# NS_ARM_Control_01_10_2018.net
KiCad netlist of a schematic drawn in EAGLE
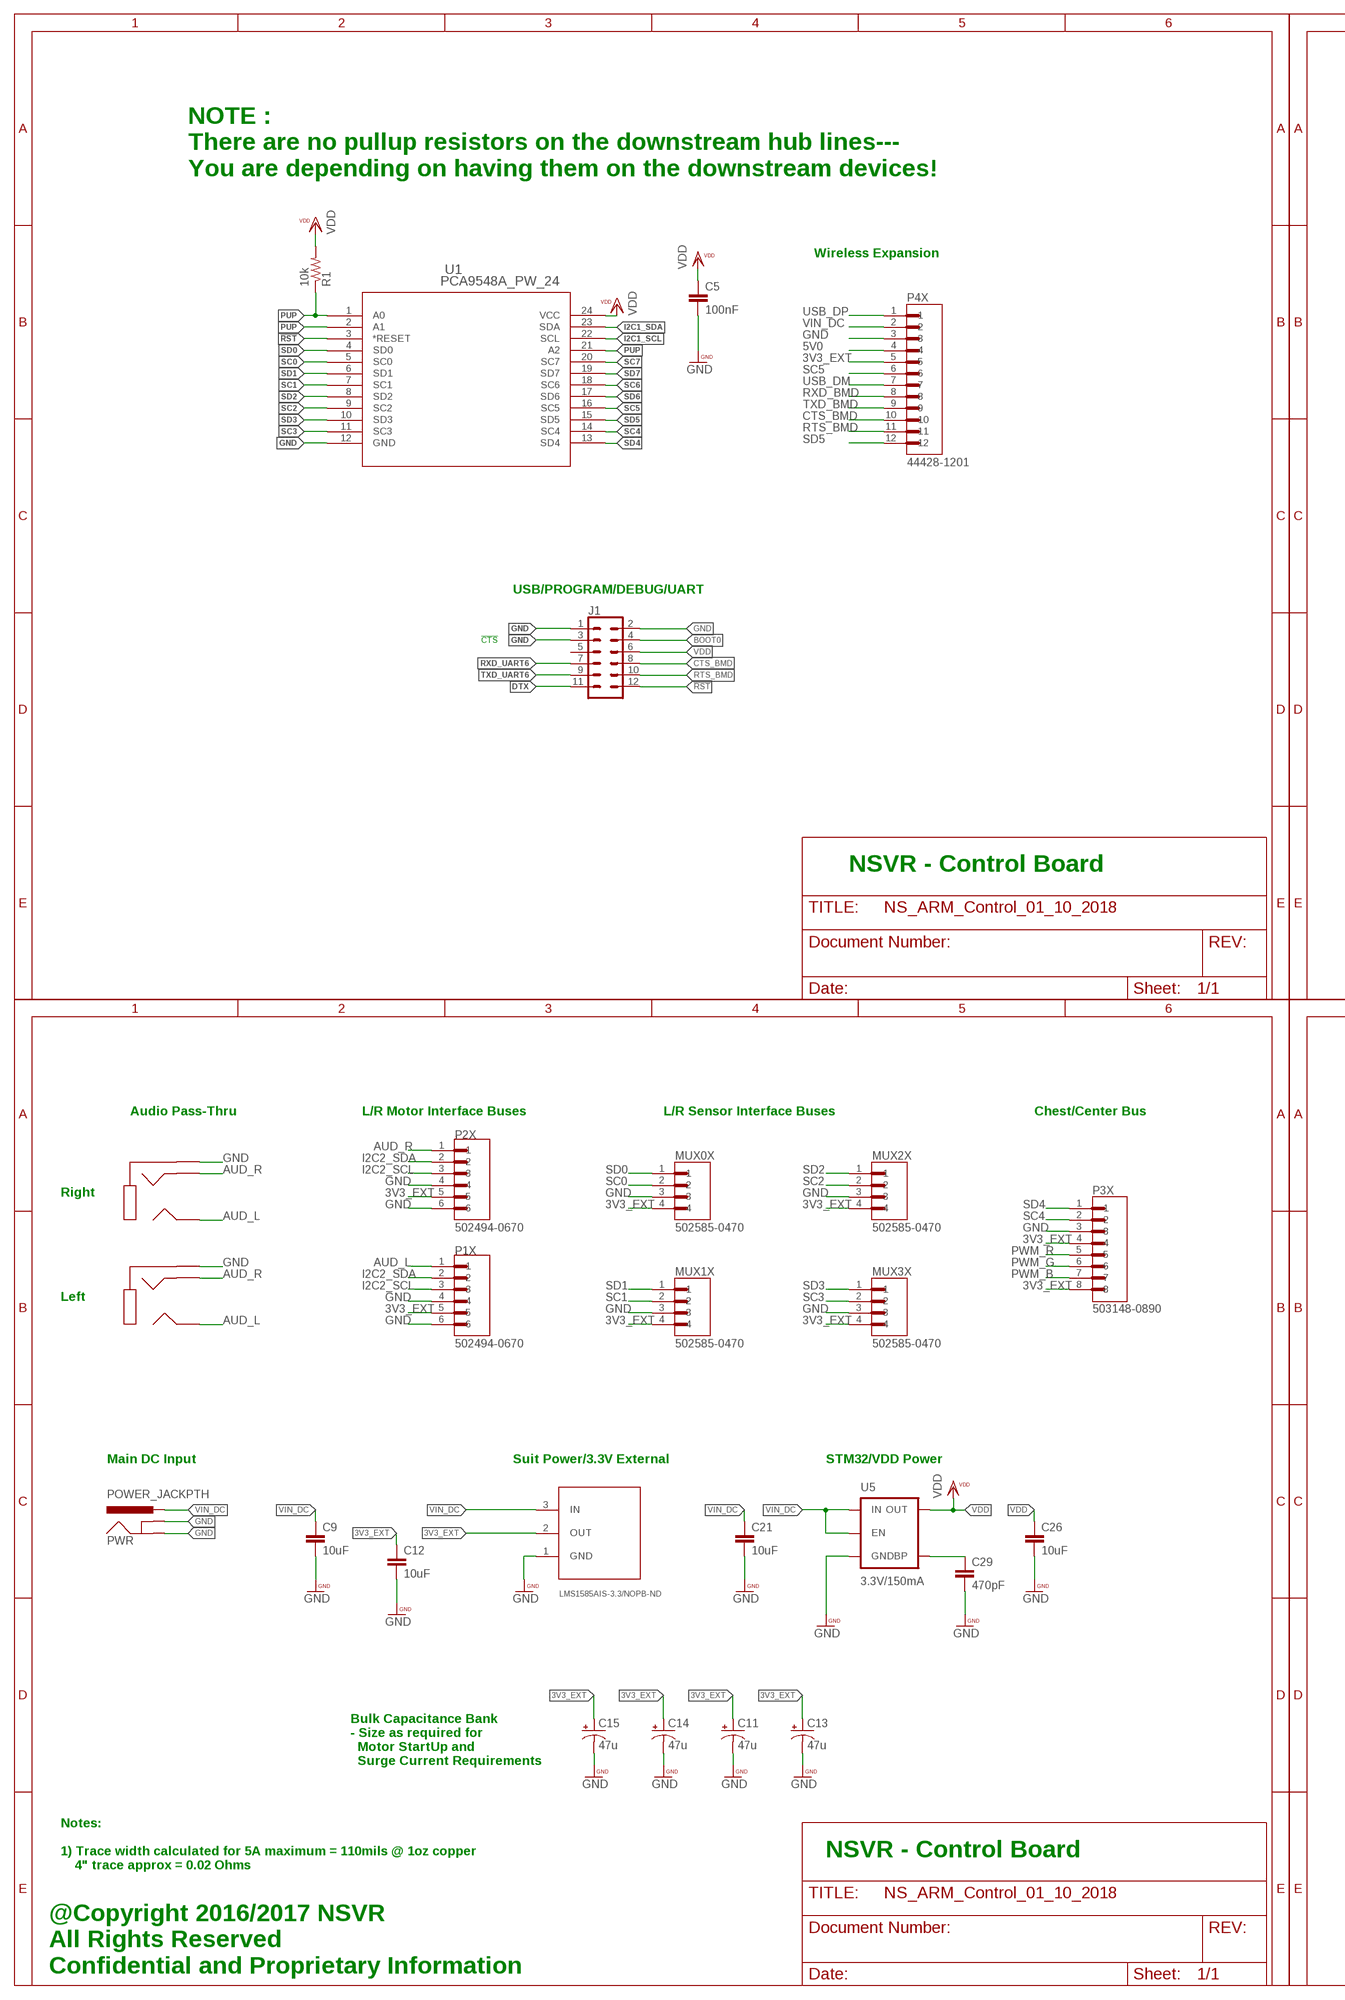
[diagram p0: schematic, sheet 1, part 1 of 2]
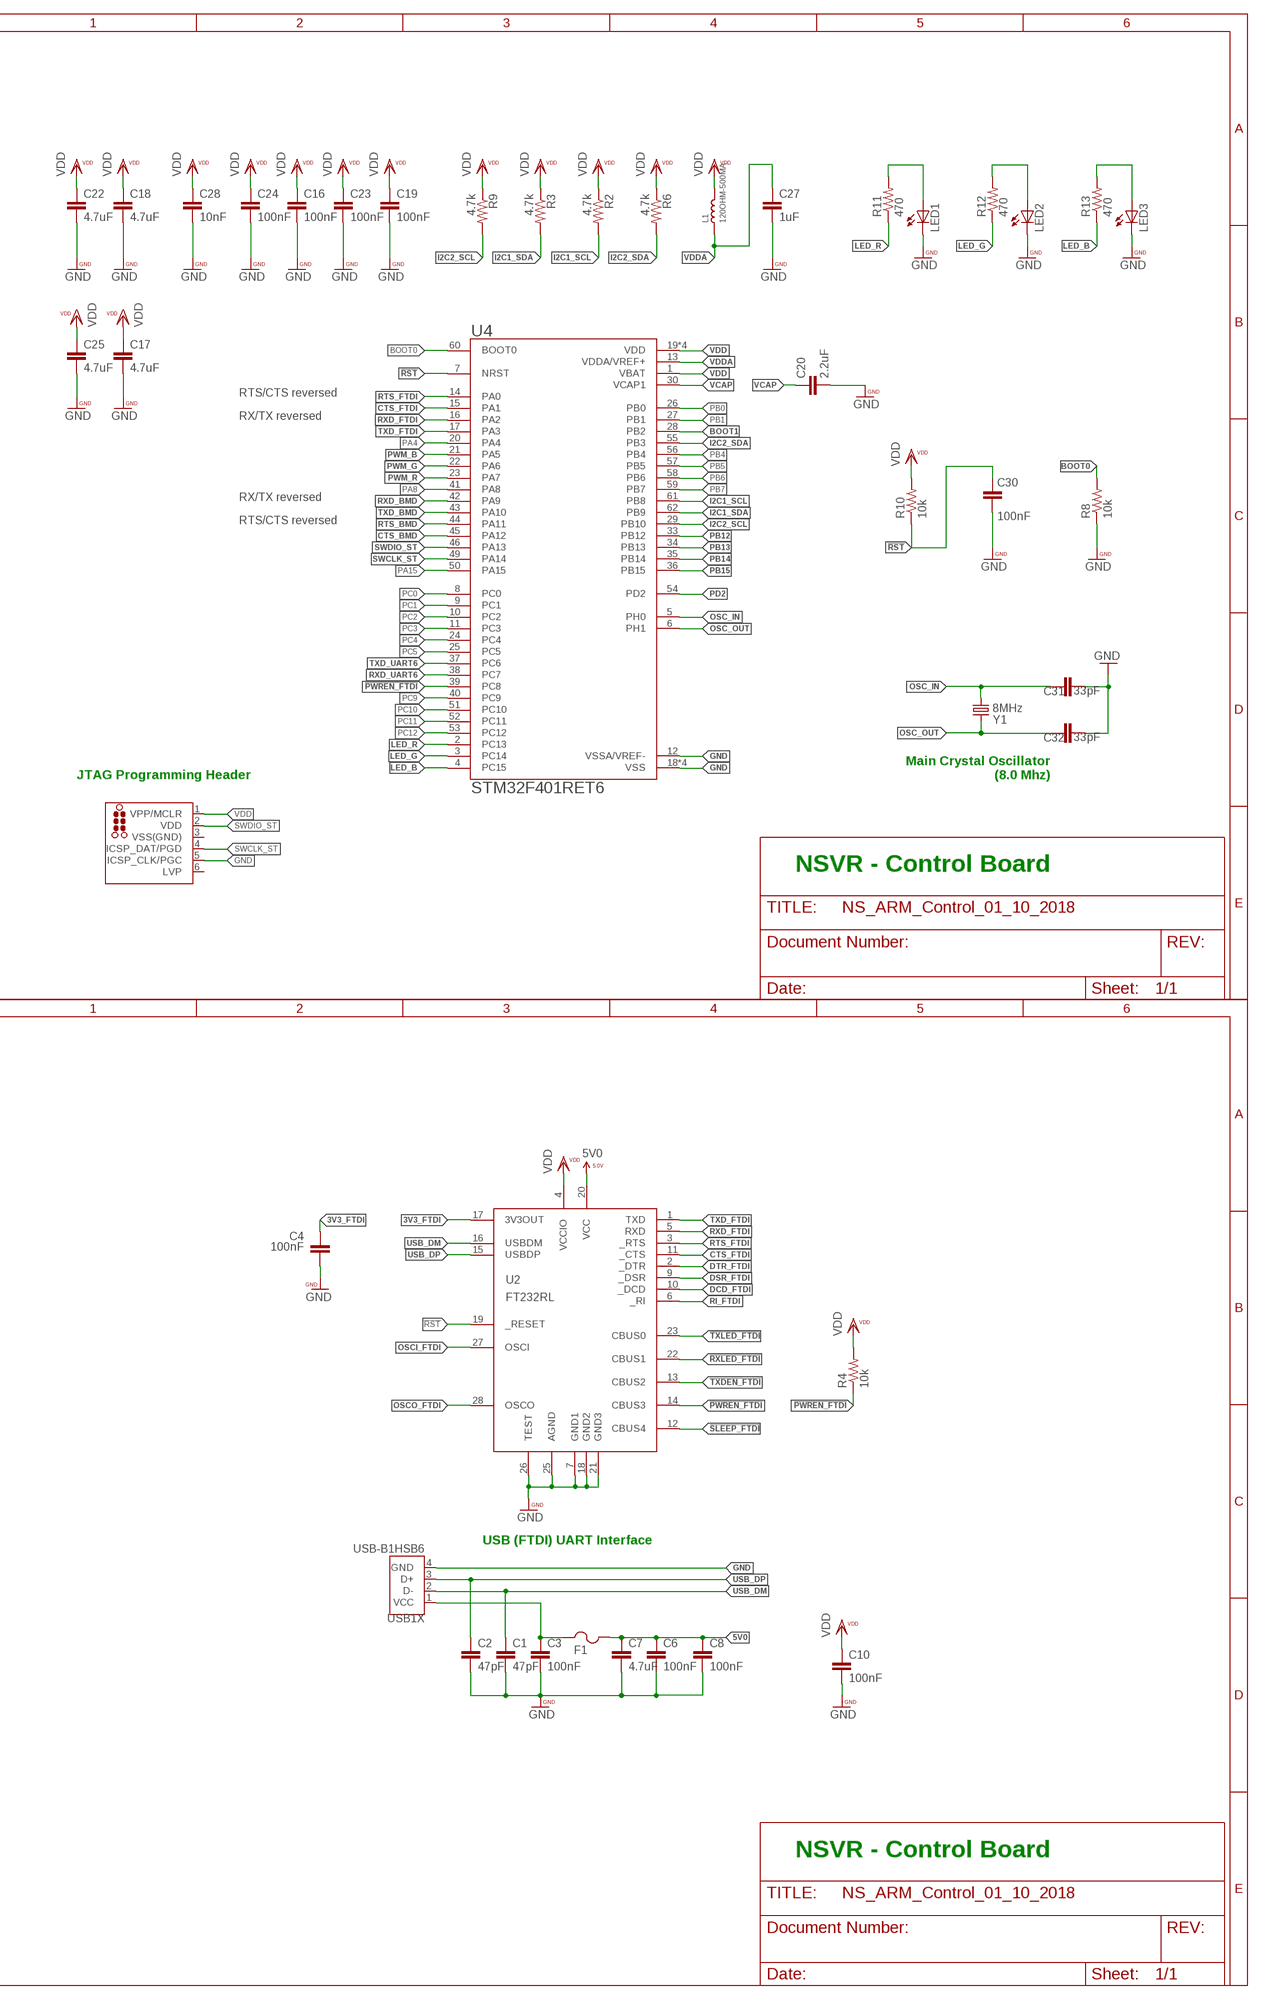
[diagram p1: schematic, sheet 1, part 2 of 2]

(export (version "E")
  (design (tool "Eeschema 10.0.6"))
  (components
    (comp (ref "C1")
      (value "47pF")
      (footprint "eagle-import:0402-CAP")
      (libsource (lib "eagle-import") (part "CAP0402-CAP"))
    )
    (comp (ref "C2")
      (value "47pF")
      (footprint "eagle-import:0402-CAP")
      (libsource (lib "eagle-import") (part "CAP0402-CAP"))
    )
    (comp (ref "C3")
      (value "100nF")
      (footprint "eagle-import:0402-CAP")
      (libsource (lib "eagle-import") (part "CAP0402-CAP"))
    )
    (comp (ref "C4")
      (value "100nF")
      (footprint "eagle-import:0402-CAP")
      (libsource (lib "eagle-import") (part "CAP0402-CAP"))
    )
    (comp (ref "C5")
      (value "100nF")
      (footprint "eagle-import:0402-CAP")
      (libsource (lib "eagle-import") (part "CAP0402-CAP"))
    )
    (comp (ref "C6")
      (value "100nF")
      (footprint "eagle-import:0402-CAP")
      (libsource (lib "eagle-import") (part "CAP0402-CAP"))
    )
    (comp (ref "C7")
      (value "4.7uF")
      (footprint "eagle-import:0402-CAP")
      (libsource (lib "eagle-import") (part "CAP0402-CAP"))
    )
    (comp (ref "C8")
      (value "100nF")
      (footprint "eagle-import:0402-CAP")
      (libsource (lib "eagle-import") (part "CAP0402-CAP"))
    )
    (comp (ref "C9")
      (value "10uF")
      (footprint "eagle-import:0603-CAP")
      (libsource (lib "eagle-import") (part "CAP0603-CAP"))
    )
    (comp (ref "C10")
      (value "100nF")
      (footprint "eagle-import:0402-CAP")
      (libsource (lib "eagle-import") (part "CAP0402-CAP"))
    )
    (comp (ref "C11")
      (value "47u")
      (footprint "eagle-import:PANASONIC_D")
      (libsource (lib "eagle-import") (part "CAP_POLD"))
    )
    (comp (ref "C12")
      (value "10uF")
      (footprint "eagle-import:0603-CAP")
      (libsource (lib "eagle-import") (part "CAP0603-CAP"))
    )
    (comp (ref "C13")
      (value "47u")
      (footprint "eagle-import:PANASONIC_D")
      (libsource (lib "eagle-import") (part "CAP_POLD"))
    )
    (comp (ref "C14")
      (value "47u")
      (footprint "eagle-import:PANASONIC_D")
      (libsource (lib "eagle-import") (part "CAP_POLD"))
    )
    (comp (ref "C15")
      (value "47u")
      (footprint "eagle-import:PANASONIC_D")
      (libsource (lib "eagle-import") (part "CAP_POLD"))
    )
    (comp (ref "C16")
      (value "100nF")
      (footprint "eagle-import:0402-CAP")
      (libsource (lib "eagle-import") (part "CAP0402-CAP"))
    )
    (comp (ref "C17")
      (value "4.7uF")
      (footprint "eagle-import:0402-CAP")
      (libsource (lib "eagle-import") (part "CAP0402-CAP"))
    )
    (comp (ref "C18")
      (value "4.7uF")
      (footprint "eagle-import:0402-CAP")
      (libsource (lib "eagle-import") (part "CAP0402-CAP"))
    )
    (comp (ref "C19")
      (value "100nF")
      (footprint "eagle-import:0402-CAP")
      (libsource (lib "eagle-import") (part "CAP0402-CAP"))
    )
    (comp (ref "C20")
      (value "2.2uF")
      (footprint "eagle-import:0402-CAP")
      (libsource (lib "eagle-import") (part "CAP0402-CAP"))
    )
    (comp (ref "C21")
      (value "10uF")
      (footprint "eagle-import:0603-CAP")
      (libsource (lib "eagle-import") (part "CAP0603-CAP"))
    )
    (comp (ref "C22")
      (value "4.7uF")
      (footprint "eagle-import:0402-CAP")
      (libsource (lib "eagle-import") (part "CAP0402-CAP"))
    )
    (comp (ref "C23")
      (value "100nF")
      (footprint "eagle-import:0402-CAP")
      (libsource (lib "eagle-import") (part "CAP0402-CAP"))
    )
    (comp (ref "C24")
      (value "100nF")
      (footprint "eagle-import:0402-CAP")
      (libsource (lib "eagle-import") (part "CAP0402-CAP"))
    )
    (comp (ref "C25")
      (value "4.7uF")
      (footprint "eagle-import:0402-CAP")
      (libsource (lib "eagle-import") (part "CAP0402-CAP"))
    )
    (comp (ref "C26")
      (value "10uF")
      (footprint "eagle-import:0603-CAP")
      (libsource (lib "eagle-import") (part "CAP0603-CAP"))
    )
    (comp (ref "C27")
      (value "1uF")
      (footprint "eagle-import:0402-CAP")
      (libsource (lib "eagle-import") (part "CAP0402-CAP"))
    )
    (comp (ref "C28")
      (value "10nF")
      (footprint "eagle-import:0402-CAP")
      (libsource (lib "eagle-import") (part "CAP0402-CAP"))
    )
    (comp (ref "C29")
      (value "470pF")
      (footprint "eagle-import:0402-CAP")
      (libsource (lib "eagle-import") (part "CAP0402-CAP"))
    )
    (comp (ref "C30")
      (value "100nF")
      (footprint "eagle-import:0402-CAP")
      (libsource (lib "eagle-import") (part "CAP0402-CAP"))
    )
    (comp (ref "C31")
      (value "33pF")
      (footprint "eagle-import:0402-CAP")
      (libsource (lib "eagle-import") (part "CAP0402-CAP"))
    )
    (comp (ref "C32")
      (value "33pF")
      (footprint "eagle-import:0402-CAP")
      (libsource (lib "eagle-import") (part "CAP0402-CAP"))
    )
    (comp (ref "F1")
      (value "1206L050YR")
      (footprint "eagle-import:1206LSERIES")
      (fields (field (name "COPYRIGHT") "Copyright C 2015 Accelerated Designs. All rights reserved"))
      (libsource (lib "eagle-import") (part "1206L050YR"))
    )
    (comp (ref "J1")
      (value "CONN_06X2SMD_FEMALE")
      (footprint "eagle-import:2X6_SMD")
      (libsource (lib "eagle-import") (part "CONN_06X2SMD_FEMALE"))
    )
    (comp (ref "J_ST")
      (value "TC2030-MCP-NL")
      (footprint "eagle-import:TC2030-MCP-NL")
      (libsource (lib "eagle-import") (part "TC2030-MCP-NL"))
    )
    (comp (ref "L1")
      (value "120OHM-500MA")
      (footprint "eagle-import:L0603")
      (fields (field (name "MPN") "BLM18AG121SN1D"))
      (libsource (lib "eagle-import") (part "SMD-FERRITE-CHIP-120-OHM-500MA(0603)"))
    )
    (comp (ref "LED1")
      (value "LEDCHIP-LED0603")
      (footprint "eagle-import:CHIP-LED0603")
      (libsource (lib "eagle-import") (part "LEDCHIP-LED0603"))
    )
    (comp (ref "LED2")
      (value "LEDCHIP-LED0603")
      (footprint "eagle-import:CHIP-LED0603")
      (libsource (lib "eagle-import") (part "LEDCHIP-LED0603"))
    )
    (comp (ref "LED3")
      (value "LEDCHIP-LED0603")
      (footprint "eagle-import:CHIP-LED0603")
      (libsource (lib "eagle-import") (part "LEDCHIP-LED0603"))
    )
    (comp (ref "MUX0X")
      (value "502585-0470")
      (footprint "eagle-import:MOLEX_502585-0470")
      (fields (field (name "MF") "Molex"))
      (libsource (lib "eagle-import") (part "502585-0470"))
    )
    (comp (ref "MUX1X")
      (value "502585-0470")
      (footprint "eagle-import:MOLEX_502585-0470")
      (fields (field (name "MF") "Molex"))
      (libsource (lib "eagle-import") (part "502585-0470"))
    )
    (comp (ref "MUX2X")
      (value "502585-0470")
      (footprint "eagle-import:MOLEX_502585-0470")
      (fields (field (name "MF") "Molex"))
      (libsource (lib "eagle-import") (part "502585-0470"))
    )
    (comp (ref "MUX3X")
      (value "502585-0470")
      (footprint "eagle-import:MOLEX_502585-0470")
      (fields (field (name "MF") "Molex"))
      (libsource (lib "eagle-import") (part "502585-0470"))
    )
    (comp (ref "P1X")
      (value "502494-0670")
      (footprint "eagle-import:MOLEX_502494-0670")
      (fields (field (name "MF") "Molex"))
      (libsource (lib "eagle-import") (part "502494-0670"))
    )
    (comp (ref "P2X")
      (value "502494-0670")
      (footprint "eagle-import:MOLEX_502494-0670")
      (fields (field (name "MF") "Molex"))
      (libsource (lib "eagle-import") (part "502494-0670"))
    )
    (comp (ref "P3X")
      (value "503148-0890")
      (footprint "eagle-import:MOLEX_503148-0890")
      (fields (field (name "MF") "Molex"))
      (libsource (lib "eagle-import") (part "503148-0890"))
    )
    (comp (ref "P4X")
      (value "44428-1201")
      (footprint "eagle-import:MOLEX_44428-1201")
      (fields (field (name "MF") "Molex"))
      (libsource (lib "eagle-import") (part "44428-1201"))
    )
    (comp (ref "PJ1")
      (value "SJ1-3513N")
      (footprint "eagle-import:SJ1-351XN")
      (libsource (lib "eagle-import") (part "SJ1-3513N"))
    )
    (comp (ref "PJ2")
      (value "SJ1-3513N")
      (footprint "eagle-import:SJ1-351XN")
      (libsource (lib "eagle-import") (part "SJ1-3513N"))
    )
    (comp (ref "PWR")
      (value "POWER_JACKPTH")
      (footprint "eagle-import:POWER_JACK_PTH")
      (libsource (lib "eagle-import") (part "POWER_JACKPTH"))
    )
    (comp (ref "R1")
      (value "10k")
      (footprint "eagle-import:EIA-0402")
      (libsource (lib "eagle-import") (part "RESISTOR0402-TYP"))
    )
    (comp (ref "R2")
      (value "4.7k")
      (footprint "eagle-import:EIA-0402")
      (libsource (lib "eagle-import") (part "RESISTOR0402-TYP"))
    )
    (comp (ref "R3")
      (value "4.7k")
      (footprint "eagle-import:EIA-0402")
      (libsource (lib "eagle-import") (part "RESISTOR0402-TYP"))
    )
    (comp (ref "R4")
      (value "10k")
      (footprint "eagle-import:EIA-0402")
      (libsource (lib "eagle-import") (part "RESISTOR0402-TYP"))
    )
    (comp (ref "R6")
      (value "4.7k")
      (footprint "eagle-import:EIA-0402")
      (libsource (lib "eagle-import") (part "RESISTOR0402-TYP"))
    )
    (comp (ref "R8")
      (value "10k")
      (footprint "eagle-import:EIA-0402")
      (libsource (lib "eagle-import") (part "RESISTOR0402-TYP"))
    )
    (comp (ref "R9")
      (value "4.7k")
      (footprint "eagle-import:EIA-0402")
      (libsource (lib "eagle-import") (part "RESISTOR0402-TYP"))
    )
    (comp (ref "R10")
      (value "10k")
      (footprint "eagle-import:EIA-0402")
      (libsource (lib "eagle-import") (part "RESISTOR0402-TYP"))
    )
    (comp (ref "R11")
      (value "470")
      (footprint "eagle-import:EIA-0402")
      (libsource (lib "eagle-import") (part "RESISTOR0402-TYP"))
    )
    (comp (ref "R12")
      (value "470")
      (footprint "eagle-import:EIA-0402")
      (libsource (lib "eagle-import") (part "RESISTOR0402-TYP"))
    )
    (comp (ref "R13")
      (value "470")
      (footprint "eagle-import:EIA-0402")
      (libsource (lib "eagle-import") (part "RESISTOR0402-TYP"))
    )
    (comp (ref "U1")
      (value "PCA9548A_PW_24")
      (footprint "eagle-import:PW24")
      (fields
        (field (name "GENERIC_PART_NUMBER") "PCA9548A")
        (field (name "MANUFACTURER") "Texas Instruments")
        (field (name "MANUFACTURER_PART_NUMBER") "pca9548a_pw_24")
      )
      (libsource (lib "eagle-import") (part "PCA9548A_PW_24"))
    )
    (comp (ref "U2")
      (value "FT232RL")
      (footprint "eagle-import:SSOP28DB")
      (libsource (lib "eagle-import") (part "FT232RL"))
    )
    (comp (ref "U3")
      (value "LMS1585AIS-3.3/NOPB-ND")
      (footprint "eagle-import:TO254P1524X483-4N")
      (libsource (lib "eagle-import") (part "LMS1585AIS-3.3/NOPB-ND"))
    )
    (comp (ref "U4")
      (value "STM32F401RET6")
      (footprint "eagle-import:QFP50P1200X1200X160-64N")
      (fields (field (name "MF") "STMicroelectronics"))
      (libsource (lib "eagle-import") (part "STM32F401RET6"))
    )
    (comp (ref "U5")
      (value "3.3V/150mA")
      (footprint "eagle-import:SOT23-5")
      (libsource (lib "eagle-import") (part "V_REG_MIC52053.3V"))
    )
    (comp (ref "USB1X")
      (value "USB-B1HSB6")
      (footprint "eagle-import:OST_USB-B1HSB6")
      (fields (field (name "MF") "On Shore Technology"))
      (libsource (lib "eagle-import") (part "USB-B1HSB6"))
    )
    (comp (ref "Y1")
      (value "8MHz")
      (footprint "eagle-import:CRYSTAL-SMD-5X3")
      (libsource (lib "eagle-import") (part "CRYSTAL5X3"))
    )
  )
  (nets
    (net (code "1") (name "/AUD_L") (class "Default")
      (node (ref "P1X") (pin "1") (pinfunction "1_1") (pintype "passive"))
      (node (ref "PJ1") (pin "2") (pinfunction "2_2") (pintype "bidirectional"))
      (node (ref "PJ2") (pin "2") (pinfunction "2_2") (pintype "bidirectional"))
    )
    (net (code "2") (name "/AUD_R") (class "Default")
      (node (ref "P2X") (pin "1") (pinfunction "1_1") (pintype "passive"))
      (node (ref "PJ1") (pin "3") (pinfunction "3_3") (pintype "bidirectional"))
      (node (ref "PJ2") (pin "3") (pinfunction "3_3") (pintype "bidirectional"))
    )
    (net (code "3") (name "/VSS(GND)") (class "Default")
      (node (ref "J_ST") (pin "3") (pinfunction "VSS(GND)_3") (pintype "power_in"))
    )
    (net (code "4") (name "/~{PWREN_FTDI}") (class "Default")
      (node (ref "R4") (pin "1") (pinfunction "1_1") (pintype "passive"))
      (node (ref "U2") (pin "14") (pinfunction "CBUS3_14") (pintype "bidirectional"))
      (node (ref "U4") (pin "39") (pinfunction "PC8_39") (pintype "bidirectional"))
    )
    (net (code "5") (name "/~{RST}") (class "Default")
      (node (ref "C30") (pin "1") (pinfunction "1_1") (pintype "passive"))
      (node (ref "J1") (pin "12") (pinfunction "12_12") (pintype "passive"))
      (node (ref "R10") (pin "1") (pinfunction "1_1") (pintype "passive"))
      (node (ref "U1") (pin "3") (pinfunction "*RESET_3") (pintype "input"))
      (node (ref "U2") (pin "19") (pinfunction "_RESET_19") (pintype "input"))
      (node (ref "U4") (pin "7") (pinfunction "NRST_7") (pintype "bidirectional"))
    )
    (net (code "6") (name "/~{RXLED_FTDI}") (class "Default")
      (node (ref "U2") (pin "22") (pinfunction "CBUS1_22") (pintype "bidirectional"))
    )
    (net (code "7") (name "/~{SLEEP_FTDI}") (class "Default")
      (node (ref "U2") (pin "12") (pinfunction "CBUS4_12") (pintype "bidirectional"))
    )
    (net (code "8") (name "/~{TXDEN_FTDI}") (class "Default")
      (node (ref "U2") (pin "13") (pinfunction "CBUS2_13") (pintype "bidirectional"))
    )
    (net (code "9") (name "/~{TXLED_FTDI}") (class "Default")
      (node (ref "U2") (pin "23") (pinfunction "CBUS0_23") (pintype "bidirectional"))
    )
    (net (code "10") (name "3V3_EXT") (class "Default")
      (node (ref "C11") (pin "+") (pinfunction "+_+") (pintype "passive"))
      (node (ref "C12") (pin "1") (pinfunction "1_1") (pintype "passive"))
      (node (ref "C13") (pin "+") (pinfunction "+_+") (pintype "passive"))
      (node (ref "C14") (pin "+") (pinfunction "+_+") (pintype "passive"))
      (node (ref "C15") (pin "+") (pinfunction "+_+") (pintype "passive"))
      (node (ref "MUX0X") (pin "4") (pinfunction "4_4") (pintype "passive"))
      (node (ref "MUX1X") (pin "4") (pinfunction "4_4") (pintype "passive"))
      (node (ref "MUX2X") (pin "4") (pinfunction "4_4") (pintype "passive"))
      (node (ref "MUX3X") (pin "4") (pinfunction "4_4") (pintype "passive"))
      (node (ref "P1X") (pin "5") (pinfunction "5_5") (pintype "passive"))
      (node (ref "P2X") (pin "5") (pinfunction "5_5") (pintype "passive"))
      (node (ref "P3X") (pin "4") (pinfunction "4_4") (pintype "passive"))
      (node (ref "P3X") (pin "8") (pinfunction "8_8") (pintype "passive"))
      (node (ref "P4X") (pin "5") (pinfunction "5_5") (pintype "passive"))
      (node (ref "U3") (pin "2") (pinfunction "OUT_2") (pintype "bidirectional"))
    )
    (net (code "11") (name "3V3_FTDI") (class "Default")
      (node (ref "C4") (pin "1") (pinfunction "1_1") (pintype "passive"))
      (node (ref "U2") (pin "17") (pinfunction "3V3OUT_17") (pintype "output"))
    )
    (net (code "12") (name "5V0") (class "Default")
      (node (ref "C6") (pin "1") (pinfunction "1_1") (pintype "passive"))
      (node (ref "C7") (pin "1") (pinfunction "1_1") (pintype "passive"))
      (node (ref "C8") (pin "1") (pinfunction "1_1") (pintype "passive"))
      (node (ref "F1") (pin "2") (pinfunction "2_2") (pintype "passive"))
      (node (ref "P4X") (pin "4") (pinfunction "4_4") (pintype "passive"))
      (node (ref "U2") (pin "20") (pinfunction "VCC_20") (pintype "power_in"))
    )
    (net (code "13") (name "BOOT0") (class "Default")
      (node (ref "J1") (pin "4") (pinfunction "4_4") (pintype "passive"))
      (node (ref "R8") (pin "2") (pinfunction "2_2") (pintype "passive"))
      (node (ref "U4") (pin "60") (pinfunction "BOOT0_60") (pintype "input"))
    )
    (net (code "14") (name "BOOT1") (class "Default")
      (node (ref "U4") (pin "28") (pinfunction "PB2_28") (pintype "bidirectional"))
    )
    (net (code "15") (name "CTS_BMD") (class "Default")
      (node (ref "J1") (pin "8") (pinfunction "8_8") (pintype "passive"))
      (node (ref "P4X") (pin "10") (pinfunction "10_10") (pintype "passive"))
      (node (ref "U4") (pin "45") (pinfunction "PA12_45") (pintype "bidirectional"))
    )
    (net (code "16") (name "CTS_FTDI") (class "Default")
      (node (ref "U2") (pin "11") (pinfunction "_CTS_11") (pintype "input"))
      (node (ref "U4") (pin "15") (pinfunction "PA1_15") (pintype "bidirectional"))
    )
    (net (code "17") (name "DCD_FTDI") (class "Default")
      (node (ref "U2") (pin "10") (pinfunction "_DCD_10") (pintype "input"))
    )
    (net (code "18") (name "DSR_FTDI") (class "Default")
      (node (ref "U2") (pin "9") (pinfunction "_DSR_9") (pintype "input"))
    )
    (net (code "19") (name "DTR_FTDI") (class "Default")
      (node (ref "U2") (pin "2") (pinfunction "_DTR_2") (pintype "output"))
    )
    (net (code "20") (name "DTX") (class "Default")
      (node (ref "J1") (pin "11") (pinfunction "11_11") (pintype "passive"))
    )
    (net (code "21") (name "GND") (class "Default")
      (node (ref "C1") (pin "2") (pinfunction "2_2") (pintype "passive"))
      (node (ref "C10") (pin "2") (pinfunction "2_2") (pintype "passive"))
      (node (ref "C11") (pin "-") (pinfunction "-_-") (pintype "passive"))
      (node (ref "C12") (pin "2") (pinfunction "2_2") (pintype "passive"))
      (node (ref "C13") (pin "-") (pinfunction "-_-") (pintype "passive"))
      (node (ref "C14") (pin "-") (pinfunction "-_-") (pintype "passive"))
      (node (ref "C15") (pin "-") (pinfunction "-_-") (pintype "passive"))
      (node (ref "C16") (pin "2") (pinfunction "2_2") (pintype "passive"))
      (node (ref "C17") (pin "2") (pinfunction "2_2") (pintype "passive"))
      (node (ref "C18") (pin "2") (pinfunction "2_2") (pintype "passive"))
      (node (ref "C19") (pin "2") (pinfunction "2_2") (pintype "passive"))
      (node (ref "C2") (pin "2") (pinfunction "2_2") (pintype "passive"))
      (node (ref "C20") (pin "2") (pinfunction "2_2") (pintype "passive"))
      (node (ref "C21") (pin "2") (pinfunction "2_2") (pintype "passive"))
      (node (ref "C22") (pin "2") (pinfunction "2_2") (pintype "passive"))
      (node (ref "C23") (pin "2") (pinfunction "2_2") (pintype "passive"))
      (node (ref "C24") (pin "2") (pinfunction "2_2") (pintype "passive"))
      (node (ref "C25") (pin "2") (pinfunction "2_2") (pintype "passive"))
      (node (ref "C26") (pin "2") (pinfunction "2_2") (pintype "passive"))
      (node (ref "C27") (pin "2") (pinfunction "2_2") (pintype "passive"))
      (node (ref "C28") (pin "2") (pinfunction "2_2") (pintype "passive"))
      (node (ref "C29") (pin "2") (pinfunction "2_2") (pintype "passive"))
      (node (ref "C3") (pin "2") (pinfunction "2_2") (pintype "passive"))
      (node (ref "C30") (pin "2") (pinfunction "2_2") (pintype "passive"))
      (node (ref "C31") (pin "1") (pinfunction "1_1") (pintype "passive"))
      (node (ref "C32") (pin "1") (pinfunction "1_1") (pintype "passive"))
      (node (ref "C4") (pin "2") (pinfunction "2_2") (pintype "passive"))
      (node (ref "C5") (pin "2") (pinfunction "2_2") (pintype "passive"))
      (node (ref "C6") (pin "2") (pinfunction "2_2") (pintype "passive"))
      (node (ref "C7") (pin "2") (pinfunction "2_2") (pintype "passive"))
      (node (ref "C8") (pin "2") (pinfunction "2_2") (pintype "passive"))
      (node (ref "C9") (pin "2") (pinfunction "2_2") (pintype "passive"))
      (node (ref "J1") (pin "1") (pinfunction "1_1") (pintype "passive"))
      (node (ref "J1") (pin "2") (pinfunction "2_2") (pintype "passive"))
      (node (ref "J1") (pin "3") (pinfunction "3_3") (pintype "passive"))
      (node (ref "J_ST") (pin "5") (pinfunction "ICSP_CLK/PGC_5") (pintype "output"))
      (node (ref "LED1") (pin "C") (pinfunction "C_C") (pintype "passive"))
      (node (ref "LED2") (pin "C") (pinfunction "C_C") (pintype "passive"))
      (node (ref "LED3") (pin "C") (pinfunction "C_C") (pintype "passive"))
      (node (ref "MUX0X") (pin "3") (pinfunction "3_3") (pintype "passive"))
      (node (ref "MUX1X") (pin "3") (pinfunction "3_3") (pintype "passive"))
      (node (ref "MUX2X") (pin "3") (pinfunction "3_3") (pintype "passive"))
      (node (ref "MUX3X") (pin "3") (pinfunction "3_3") (pintype "passive"))
      (node (ref "P1X") (pin "4") (pinfunction "4_4") (pintype "passive"))
      (node (ref "P1X") (pin "6") (pinfunction "6_6") (pintype "passive"))
      (node (ref "P2X") (pin "4") (pinfunction "4_4") (pintype "passive"))
      (node (ref "P2X") (pin "6") (pinfunction "6_6") (pintype "passive"))
      (node (ref "P3X") (pin "3") (pinfunction "3_3") (pintype "passive"))
      (node (ref "P4X") (pin "3") (pinfunction "3_3") (pintype "passive"))
      (node (ref "PJ1") (pin "1") (pinfunction "1_1") (pintype "bidirectional"))
      (node (ref "PJ2") (pin "1") (pinfunction "1_1") (pintype "bidirectional"))
      (node (ref "PWR") (pin "GND") (pinfunction "GND_GND") (pintype "bidirectional"))
      (node (ref "PWR") (pin "GNDBREAK") (pinfunction "GNDBREAK_GNDBREAK") (pintype "bidirectional"))
      (node (ref "R8") (pin "1") (pinfunction "1_1") (pintype "passive"))
      (node (ref "U1") (pin "12") (pinfunction "GND_12") (pintype "power_in"))
      (node (ref "U2") (pin "18") (pinfunction "GND2_18") (pintype "power_in"))
      (node (ref "U2") (pin "21") (pinfunction "GND3_21") (pintype "power_in"))
      (node (ref "U2") (pin "25") (pinfunction "AGND_25") (pintype "power_in"))
      (node (ref "U2") (pin "26") (pinfunction "TEST_26") (pintype "input"))
      (node (ref "U2") (pin "7") (pinfunction "GND1_7") (pintype "power_in"))
      (node (ref "U3") (pin "1") (pinfunction "GND_1") (pintype "bidirectional"))
      (node (ref "U4") (pin "12") (pinfunction "VSSA/VREF-_12") (pintype "power_in"))
      (node (ref "U4") (pin "18") (pinfunction "VSS_18") (pintype "power_in"))
      (node (ref "U4") (pin "31") (pinfunction "VSS_31") (pintype "power_in"))
      (node (ref "U4") (pin "47") (pinfunction "VSS_47") (pintype "power_in"))
      (node (ref "U4") (pin "63") (pinfunction "VSS_63") (pintype "power_in"))
      (node (ref "U5") (pin "2") (pinfunction "GND_2") (pintype "input"))
      (node (ref "USB1X") (pin "4") (pinfunction "GND_4") (pintype "power_in"))
    )
    (net (code "22") (name "I2C1_SCL") (class "Default")
      (node (ref "R2") (pin "2") (pinfunction "2_2") (pintype "passive"))
      (node (ref "U1") (pin "22") (pinfunction "SCL_22") (pintype "passive"))
      (node (ref "U4") (pin "61") (pinfunction "PB8_61") (pintype "bidirectional"))
    )
    (net (code "23") (name "I2C1_SDA") (class "Default")
      (node (ref "R3") (pin "2") (pinfunction "2_2") (pintype "passive"))
      (node (ref "U1") (pin "23") (pinfunction "SDA_23") (pintype "passive"))
      (node (ref "U4") (pin "62") (pinfunction "PB9_62") (pintype "bidirectional"))
    )
    (net (code "24") (name "I2C2_SCL") (class "Default")
      (node (ref "P1X") (pin "3") (pinfunction "3_3") (pintype "passive"))
      (node (ref "P2X") (pin "3") (pinfunction "3_3") (pintype "passive"))
      (node (ref "R9") (pin "2") (pinfunction "2_2") (pintype "passive"))
      (node (ref "U4") (pin "29") (pinfunction "PB10_29") (pintype "bidirectional"))
    )
    (net (code "25") (name "I2C2_SDA") (class "Default")
      (node (ref "P1X") (pin "2") (pinfunction "2_2") (pintype "passive"))
      (node (ref "P2X") (pin "2") (pinfunction "2_2") (pintype "passive"))
      (node (ref "R6") (pin "2") (pinfunction "2_2") (pintype "passive"))
      (node (ref "U4") (pin "55") (pinfunction "PB3_55") (pintype "bidirectional"))
    )
    (net (code "26") (name "LED_B") (class "Default")
      (node (ref "R13") (pin "1") (pinfunction "1_1") (pintype "passive"))
      (node (ref "U4") (pin "4") (pinfunction "PC15_4") (pintype "bidirectional"))
    )
    (net (code "27") (name "LED_G") (class "Default")
      (node (ref "R12") (pin "1") (pinfunction "1_1") (pintype "passive"))
      (node (ref "U4") (pin "3") (pinfunction "PC14_3") (pintype "bidirectional"))
    )
    (net (code "28") (name "LED_R") (class "Default")
      (node (ref "R11") (pin "1") (pinfunction "1_1") (pintype "passive"))
      (node (ref "U4") (pin "2") (pinfunction "PC13_2") (pintype "bidirectional"))
    )
    (net (code "29") (name "Net-(LED1-PadA)") (class "Default")
      (node (ref "LED1") (pin "A") (pinfunction "A_A") (pintype "passive"))
      (node (ref "R11") (pin "2") (pinfunction "2_2") (pintype "passive"))
    )
    (net (code "30") (name "Net-(LED2-PadA)") (class "Default")
      (node (ref "LED2") (pin "A") (pinfunction "A_A") (pintype "passive"))
      (node (ref "R12") (pin "2") (pinfunction "2_2") (pintype "passive"))
    )
    (net (code "31") (name "Net-(LED3-PadA)") (class "Default")
      (node (ref "LED3") (pin "A") (pinfunction "A_A") (pintype "passive"))
      (node (ref "R13") (pin "2") (pinfunction "2_2") (pintype "passive"))
    )
    (net (code "32") (name "Net-(U5-BP)") (class "Default")
      (node (ref "C29") (pin "1") (pinfunction "1_1") (pintype "passive"))
      (node (ref "U5") (pin "4") (pinfunction "BP_4") (pintype "input"))
    )
    (net (code "33") (name "Net-(USB1X-VCC)") (class "Default")
      (node (ref "C3") (pin "1") (pinfunction "1_1") (pintype "passive"))
      (node (ref "F1") (pin "1") (pinfunction "1_1") (pintype "passive"))
      (node (ref "USB1X") (pin "1") (pinfunction "VCC_1") (pintype "power_in"))
    )
    (net (code "34") (name "OSCI_FTDI") (class "Default")
      (node (ref "U2") (pin "27") (pinfunction "OSCI_27") (pintype "input"))
    )
    (net (code "35") (name "OSCO_FTDI") (class "Default")
      (node (ref "U2") (pin "28") (pinfunction "OSCO_28") (pintype "output"))
    )
    (net (code "36") (name "OSC_IN") (class "Default")
      (node (ref "C31") (pin "2") (pinfunction "2_2") (pintype "passive"))
      (node (ref "U4") (pin "5") (pinfunction "PH0_5") (pintype "bidirectional"))
      (node (ref "Y1") (pin "1") (pinfunction "1_1") (pintype "passive"))
    )
    (net (code "37") (name "OSC_OUT") (class "Default")
      (node (ref "C32") (pin "2") (pinfunction "2_2") (pintype "passive"))
      (node (ref "U4") (pin "6") (pinfunction "PH1_6") (pintype "bidirectional"))
      (node (ref "Y1") (pin "3") (pinfunction "2_3") (pintype "passive"))
    )
    (net (code "38") (name "PA4") (class "Default")
      (node (ref "U4") (pin "20") (pinfunction "PA4_20") (pintype "bidirectional"))
    )
    (net (code "39") (name "PA8") (class "Default")
      (node (ref "U4") (pin "41") (pinfunction "PA8_41") (pintype "bidirectional"))
    )
    (net (code "40") (name "PA15") (class "Default")
      (node (ref "U4") (pin "50") (pinfunction "PA15_50") (pintype "bidirectional"))
    )
    (net (code "41") (name "PB0") (class "Default")
      (node (ref "U4") (pin "26") (pinfunction "PB0_26") (pintype "bidirectional"))
    )
    (net (code "42") (name "PB1") (class "Default")
      (node (ref "U4") (pin "27") (pinfunction "PB1_27") (pintype "bidirectional"))
    )
    (net (code "43") (name "PB4") (class "Default")
      (node (ref "U4") (pin "56") (pinfunction "PB4_56") (pintype "bidirectional"))
    )
    (net (code "44") (name "PB5") (class "Default")
      (node (ref "U4") (pin "57") (pinfunction "PB5_57") (pintype "bidirectional"))
    )
    (net (code "45") (name "PB6") (class "Default")
      (node (ref "U4") (pin "58") (pinfunction "PB6_58") (pintype "bidirectional"))
    )
    (net (code "46") (name "PB7") (class "Default")
      (node (ref "U4") (pin "59") (pinfunction "PB7_59") (pintype "bidirectional"))
    )
    (net (code "47") (name "PB12") (class "Default")
      (node (ref "U4") (pin "33") (pinfunction "PB12_33") (pintype "bidirectional"))
    )
    (net (code "48") (name "PB13") (class "Default")
      (node (ref "U4") (pin "34") (pinfunction "PB13_34") (pintype "bidirectional"))
    )
    (net (code "49") (name "PB14") (class "Default")
      (node (ref "U4") (pin "35") (pinfunction "PB14_35") (pintype "bidirectional"))
    )
    (net (code "50") (name "PB15") (class "Default")
      (node (ref "U4") (pin "36") (pinfunction "PB15_36") (pintype "bidirectional"))
    )
    (net (code "51") (name "PC0") (class "Default")
      (node (ref "U4") (pin "8") (pinfunction "PC0_8") (pintype "bidirectional"))
    )
    (net (code "52") (name "PC1") (class "Default")
      (node (ref "U4") (pin "9") (pinfunction "PC1_9") (pintype "bidirectional"))
    )
    (net (code "53") (name "PC2") (class "Default")
      (node (ref "U4") (pin "10") (pinfunction "PC2_10") (pintype "bidirectional"))
    )
    (net (code "54") (name "PC3") (class "Default")
      (node (ref "U4") (pin "11") (pinfunction "PC3_11") (pintype "bidirectional"))
    )
    (net (code "55") (name "PC4") (class "Default")
      (node (ref "U4") (pin "24") (pinfunction "PC4_24") (pintype "bidirectional"))
    )
    (net (code "56") (name "PC5") (class "Default")
      (node (ref "U4") (pin "25") (pinfunction "PC5_25") (pintype "bidirectional"))
    )
    (net (code "57") (name "PC9") (class "Default")
      (node (ref "U4") (pin "40") (pinfunction "PC9_40") (pintype "bidirectional"))
    )
    (net (code "58") (name "PC10") (class "Default")
      (node (ref "U4") (pin "51") (pinfunction "PC10_51") (pintype "bidirectional"))
    )
    (net (code "59") (name "PC11") (class "Default")
      (node (ref "U4") (pin "52") (pinfunction "PC11_52") (pintype "bidirectional"))
    )
    (net (code "60") (name "PC12") (class "Default")
      (node (ref "U4") (pin "53") (pinfunction "PC12_53") (pintype "bidirectional"))
    )
    (net (code "61") (name "PD2") (class "Default")
      (node (ref "U4") (pin "54") (pinfunction "PD2_54") (pintype "bidirectional"))
    )
    (net (code "62") (name "PUP") (class "Default")
      (node (ref "R1") (pin "1") (pinfunction "1_1") (pintype "passive"))
      (node (ref "U1") (pin "1") (pinfunction "A0_1") (pintype "input"))
      (node (ref "U1") (pin "2") (pinfunction "A1_2") (pintype "input"))
      (node (ref "U1") (pin "21") (pinfunction "A2_21") (pintype "input"))
    )
    (net (code "63") (name "PWM_B") (class "Default")
      (node (ref "P3X") (pin "7") (pinfunction "7_7") (pintype "passive"))
      (node (ref "U4") (pin "21") (pinfunction "PA5_21") (pintype "bidirectional"))
    )
    (net (code "64") (name "PWM_G") (class "Default")
      (node (ref "P3X") (pin "6") (pinfunction "6_6") (pintype "passive"))
      (node (ref "U4") (pin "22") (pinfunction "PA6_22") (pintype "bidirectional"))
    )
    (net (code "65") (name "PWM_R") (class "Default")
      (node (ref "P3X") (pin "5") (pinfunction "5_5") (pintype "passive"))
      (node (ref "U4") (pin "23") (pinfunction "PA7_23") (pintype "bidirectional"))
    )
    (net (code "66") (name "RI_FTDI") (class "Default")
      (node (ref "U2") (pin "6") (pinfunction "_RI_6") (pintype "input"))
    )
    (net (code "67") (name "RTS_BMD") (class "Default")
      (node (ref "J1") (pin "10") (pinfunction "10_10") (pintype "passive"))
      (node (ref "P4X") (pin "11") (pinfunction "11_11") (pintype "passive"))
      (node (ref "U4") (pin "44") (pinfunction "PA11_44") (pintype "bidirectional"))
    )
    (net (code "68") (name "RTS_FTDI") (class "Default")
      (node (ref "U2") (pin "3") (pinfunction "_RTS_3") (pintype "output"))
      (node (ref "U4") (pin "14") (pinfunction "PA0_14") (pintype "bidirectional"))
    )
    (net (code "69") (name "RXD_BMD") (class "Default")
      (node (ref "P4X") (pin "8") (pinfunction "8_8") (pintype "passive"))
      (node (ref "U4") (pin "42") (pinfunction "PA9_42") (pintype "bidirectional"))
    )
    (net (code "70") (name "RXD_FTDI") (class "Default")
      (node (ref "U2") (pin "5") (pinfunction "RXD_5") (pintype "input"))
      (node (ref "U4") (pin "16") (pinfunction "PA2_16") (pintype "bidirectional"))
    )
    (net (code "71") (name "RXD_UART6") (class "Default")
      (node (ref "J1") (pin "7") (pinfunction "7_7") (pintype "passive"))
      (node (ref "U4") (pin "38") (pinfunction "PC7_38") (pintype "bidirectional"))
    )
    (net (code "72") (name "SC0") (class "Default")
      (node (ref "MUX0X") (pin "2") (pinfunction "2_2") (pintype "passive"))
      (node (ref "U1") (pin "5") (pinfunction "SC0_5") (pintype "passive"))
    )
    (net (code "73") (name "SC1") (class "Default")
      (node (ref "MUX1X") (pin "2") (pinfunction "2_2") (pintype "passive"))
      (node (ref "U1") (pin "7") (pinfunction "SC1_7") (pintype "passive"))
    )
    (net (code "74") (name "SC2") (class "Default")
      (node (ref "MUX2X") (pin "2") (pinfunction "2_2") (pintype "passive"))
      (node (ref "U1") (pin "9") (pinfunction "SC2_9") (pintype "passive"))
    )
    (net (code "75") (name "SC3") (class "Default")
      (node (ref "MUX3X") (pin "2") (pinfunction "2_2") (pintype "passive"))
      (node (ref "U1") (pin "11") (pinfunction "SC3_11") (pintype "passive"))
    )
    (net (code "76") (name "SC4") (class "Default")
      (node (ref "P3X") (pin "2") (pinfunction "2_2") (pintype "passive"))
      (node (ref "U1") (pin "14") (pinfunction "SC4_14") (pintype "passive"))
    )
    (net (code "77") (name "SC5") (class "Default")
      (node (ref "P4X") (pin "6") (pinfunction "6_6") (pintype "passive"))
      (node (ref "U1") (pin "16") (pinfunction "SC5_16") (pintype "passive"))
    )
    (net (code "78") (name "SC6") (class "Default")
      (node (ref "U1") (pin "18") (pinfunction "SC6_18") (pintype "passive"))
    )
    (net (code "79") (name "SC7") (class "Default")
      (node (ref "U1") (pin "20") (pinfunction "SC7_20") (pintype "passive"))
    )
    (net (code "80") (name "SD0") (class "Default")
      (node (ref "MUX0X") (pin "1") (pinfunction "1_1") (pintype "passive"))
      (node (ref "U1") (pin "4") (pinfunction "SD0_4") (pintype "passive"))
    )
    (net (code "81") (name "SD1") (class "Default")
      (node (ref "MUX1X") (pin "1") (pinfunction "1_1") (pintype "passive"))
      (node (ref "U1") (pin "6") (pinfunction "SD1_6") (pintype "passive"))
    )
    (net (code "82") (name "SD2") (class "Default")
      (node (ref "MUX2X") (pin "1") (pinfunction "1_1") (pintype "passive"))
      (node (ref "U1") (pin "8") (pinfunction "SD2_8") (pintype "passive"))
    )
    (net (code "83") (name "SD3") (class "Default")
      (node (ref "MUX3X") (pin "1") (pinfunction "1_1") (pintype "passive"))
      (node (ref "U1") (pin "10") (pinfunction "SD3_10") (pintype "passive"))
    )
    (net (code "84") (name "SD4") (class "Default")
      (node (ref "P3X") (pin "1") (pinfunction "1_1") (pintype "passive"))
      (node (ref "U1") (pin "13") (pinfunction "SD4_13") (pintype "passive"))
    )
    (net (code "85") (name "SD5") (class "Default")
      (node (ref "P4X") (pin "12") (pinfunction "12_12") (pintype "passive"))
      (node (ref "U1") (pin "15") (pinfunction "SD5_15") (pintype "passive"))
    )
    (net (code "86") (name "SD6") (class "Default")
      (node (ref "U1") (pin "17") (pinfunction "SD6_17") (pintype "passive"))
    )
    (net (code "87") (name "SD7") (class "Default")
      (node (ref "U1") (pin "19") (pinfunction "SD7_19") (pintype "passive"))
    )
    (net (code "88") (name "SWCLK_ST") (class "Default")
      (node (ref "J_ST") (pin "4") (pinfunction "ICSP_DAT/PGD_4") (pintype "bidirectional"))
      (node (ref "U4") (pin "49") (pinfunction "PA14_49") (pintype "bidirectional"))
    )
    (net (code "89") (name "SWDIO_ST") (class "Default")
      (node (ref "J_ST") (pin "2") (pinfunction "VDD_2") (pintype "power_in"))
      (node (ref "U4") (pin "46") (pinfunction "PA13_46") (pintype "bidirectional"))
    )
    (net (code "90") (name "TXD_BMD") (class "Default")
      (node (ref "P4X") (pin "9") (pinfunction "9_9") (pintype "passive"))
      (node (ref "U4") (pin "43") (pinfunction "PA10_43") (pintype "bidirectional"))
    )
    (net (code "91") (name "TXD_FTDI") (class "Default")
      (node (ref "U2") (pin "1") (pinfunction "TXD_1") (pintype "output"))
      (node (ref "U4") (pin "17") (pinfunction "PA3_17") (pintype "bidirectional"))
    )
    (net (code "92") (name "TXD_UART6") (class "Default")
      (node (ref "J1") (pin "9") (pinfunction "9_9") (pintype "passive"))
      (node (ref "U4") (pin "37") (pinfunction "PC6_37") (pintype "bidirectional"))
    )
    (net (code "93") (name "USB_DM") (class "Default")
      (node (ref "C1") (pin "1") (pinfunction "1_1") (pintype "passive"))
      (node (ref "P4X") (pin "7") (pinfunction "7_7") (pintype "passive"))
      (node (ref "U2") (pin "16") (pinfunction "USBDM_16") (pintype "bidirectional"))
      (node (ref "USB1X") (pin "2") (pinfunction "D-_2") (pintype "bidirectional"))
    )
    (net (code "94") (name "USB_DP") (class "Default")
      (node (ref "C2") (pin "1") (pinfunction "1_1") (pintype "passive"))
      (node (ref "P4X") (pin "1") (pinfunction "1_1") (pintype "passive"))
      (node (ref "U2") (pin "15") (pinfunction "USBDP_15") (pintype "bidirectional"))
      (node (ref "USB1X") (pin "3") (pinfunction "D+_3") (pintype "bidirectional"))
    )
    (net (code "95") (name "VCAP") (class "Default")
      (node (ref "C20") (pin "1") (pinfunction "1_1") (pintype "passive"))
      (node (ref "U4") (pin "30") (pinfunction "VCAP1_30") (pintype "power_in"))
    )
    (net (code "96") (name "VDD") (class "Default")
      (node (ref "C10") (pin "1") (pinfunction "1_1") (pintype "passive"))
      (node (ref "C16") (pin "1") (pinfunction "1_1") (pintype "passive"))
      (node (ref "C17") (pin "1") (pinfunction "1_1") (pintype "passive"))
      (node (ref "C18") (pin "1") (pinfunction "1_1") (pintype "passive"))
      (node (ref "C19") (pin "1") (pinfunction "1_1") (pintype "passive"))
      (node (ref "C22") (pin "1") (pinfunction "1_1") (pintype "passive"))
      (node (ref "C23") (pin "1") (pinfunction "1_1") (pintype "passive"))
      (node (ref "C24") (pin "1") (pinfunction "1_1") (pintype "passive"))
      (node (ref "C25") (pin "1") (pinfunction "1_1") (pintype "passive"))
      (node (ref "C26") (pin "1") (pinfunction "1_1") (pintype "passive"))
      (node (ref "C28") (pin "1") (pinfunction "1_1") (pintype "passive"))
      (node (ref "C5") (pin "1") (pinfunction "1_1") (pintype "passive"))
      (node (ref "J1") (pin "6") (pinfunction "6_6") (pintype "passive"))
      (node (ref "J_ST") (pin "1") (pinfunction "VPP/MCLR_1") (pintype "passive"))
      (node (ref "L1") (pin "2") (pinfunction "2_2") (pintype "passive"))
      (node (ref "R1") (pin "2") (pinfunction "2_2") (pintype "passive"))
      (node (ref "R10") (pin "2") (pinfunction "2_2") (pintype "passive"))
      (node (ref "R2") (pin "1") (pinfunction "1_1") (pintype "passive"))
      (node (ref "R3") (pin "1") (pinfunction "1_1") (pintype "passive"))
      (node (ref "R4") (pin "2") (pinfunction "2_2") (pintype "passive"))
      (node (ref "R6") (pin "1") (pinfunction "1_1") (pintype "passive"))
      (node (ref "R9") (pin "1") (pinfunction "1_1") (pintype "passive"))
      (node (ref "U1") (pin "24") (pinfunction "VCC_24") (pintype "power_in"))
      (node (ref "U2") (pin "4") (pinfunction "VCCIO_4") (pintype "power_in"))
      (node (ref "U4") (pin "1") (pinfunction "VBAT_1") (pintype "power_in"))
      (node (ref "U4") (pin "19") (pinfunction "VDD_19") (pintype "power_in"))
      (node (ref "U4") (pin "32") (pinfunction "VDD_32") (pintype "power_in"))
      (node (ref "U4") (pin "48") (pinfunction "VDD_48") (pintype "power_in"))
      (node (ref "U4") (pin "64") (pinfunction "VDD_64") (pintype "power_in"))
      (node (ref "U5") (pin "5") (pinfunction "OUT_5") (pintype "passive"))
    )
    (net (code "97") (name "VDDA") (class "Default")
      (node (ref "C27") (pin "1") (pinfunction "1_1") (pintype "passive"))
      (node (ref "L1") (pin "1") (pinfunction "1_1") (pintype "passive"))
      (node (ref "U4") (pin "13") (pinfunction "VDDA/VREF+_13") (pintype "power_in"))
    )
    (net (code "98") (name "VIN_DC") (class "Default")
      (node (ref "C21") (pin "1") (pinfunction "1_1") (pintype "passive"))
      (node (ref "C9") (pin "1") (pinfunction "1_1") (pintype "passive"))
      (node (ref "P4X") (pin "2") (pinfunction "2_2") (pintype "passive"))
      (node (ref "PWR") (pin "PWR") (pinfunction "PWR_PWR") (pintype "bidirectional"))
      (node (ref "U3") (pin "3") (pinfunction "IN_3") (pintype "bidirectional"))
      (node (ref "U5") (pin "1") (pinfunction "IN_1") (pintype "input"))
      (node (ref "U5") (pin "3") (pinfunction "EN_3") (pintype "input"))
    )
    (net (code "99") (name "unconnected-(J1-Pad5)") (class "Default")
      (node (ref "J1") (pin "5") (pinfunction "5_5") (pintype "passive"))
    )
    (net (code "100") (name "unconnected-(J_ST-LVP-Pad6)") (class "Default")
      (node (ref "J_ST") (pin "6") (pinfunction "LVP_6") (pintype "bidirectional"))
    )
  )
)
